# 102711.net
KiCad netlist of a schematic drawn in Altium Designer
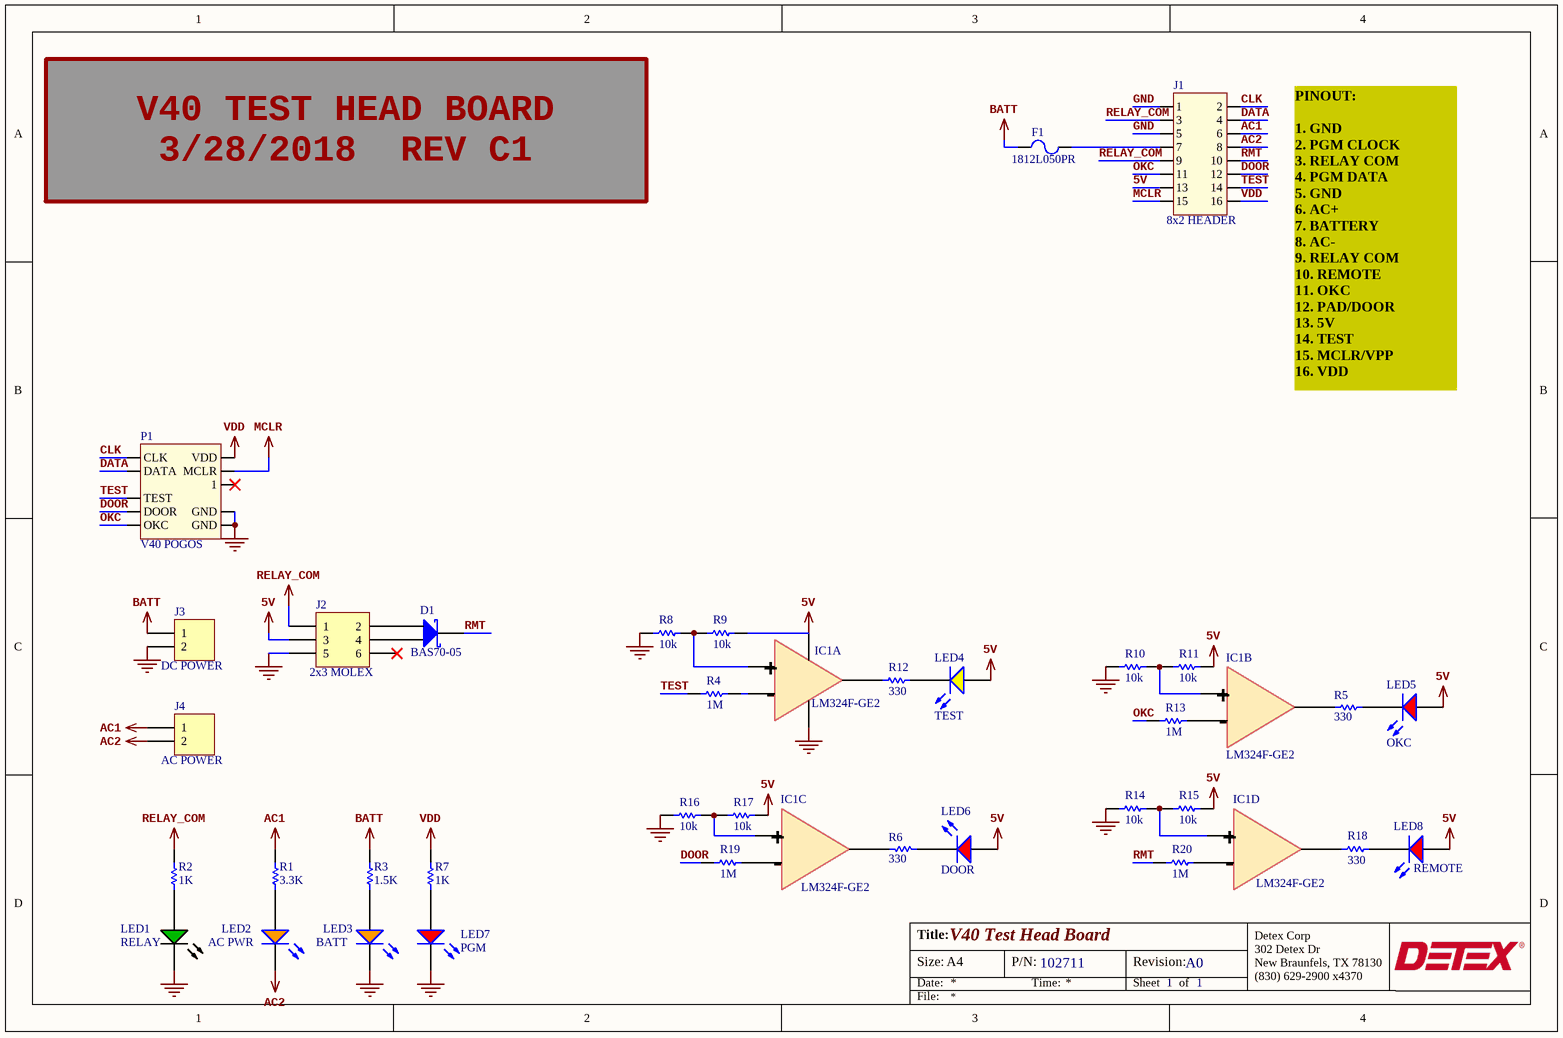
[diagram p0: 102711.SchDoc]

(export (version "E")
  (design (tool "Eeschema 10.0.6"))
  (components
    (comp (ref "D1")
      (value "BAS70-05")
      (footprint "SOT-23_M")
      (description "Dual Schottky Diode")
      (fields (field (name "MFR") "DIODES, INC"))
      (libsource (lib "Miscellaneous Devices") (part "D Schottky"))
    )
    (comp (ref "F1")
      (value "1812L050PR")
      (footprint "LFUS-1812L050_V")
      (fields (field (name "TOLERANCE") "1%"))
      (libsource (lib "Altium Content Vault") (part "CMP-1700-00002-1"))
    )
    (comp (ref "IC1")
      (value "LM324F-GE2")
      (footprint "SOIC14")
      (description "Quad Operational Amplifier 3-32V")
      (libsource (lib "102711") (part "LM324F-GE2_1"))
    )
    (comp (ref "J1")
      (value "2x8 Header")
      (footprint "HDR2X8")
      (fields (field (name "DESC") "8x2 HEADER"))
      (libsource (lib "102709") (part "2x9 Header"))
    )
    (comp (ref "J2")
      (value "2x3 MOLEX")
      (footprint "HDR2X3")
      (description "Header, 3-Pin, Dual row")
      (fields (field (name "PUBLISHER") "Altium Limited"))
      (libsource (lib "Miscellaneous Connectors") (part "Header 3X2"))
    )
    (comp (ref "J3")
      (value "DC POWER")
      (footprint "BAT_CONN")
      (description "Header, 2-Pin")
      (fields (field (name "PUBLISHER") "Altium Limited"))
      (libsource (lib "Miscellaneous Connectors") (part "Header 2"))
    )
    (comp (ref "J4")
      (value "AC POWER")
      (footprint "HDR1X2")
      (description "Header, 2-Pin")
      (fields (field (name "PUBLISHER") "Altium Limited"))
      (libsource (lib "Miscellaneous Connectors") (part "Header 2"))
    )
    (comp (ref "LED1")
      (value "RELAY")
      (footprint "LTST-C170YKT_V")
      (description "LED Uni-Color Green, 100 mW, 5 V, -55 to 85 degC, 2-Pin SMD, RoHS, Tape and Reel")
      (libsource (lib "altium-import") (part "root_3_CMP-1674-00007-1_"))
    )
    (comp (ref "LED2")
      (value "AC PWR")
      (footprint "LTST-C170YKT_V")
      (libsource (lib "altium-import") (part "root_3_SYM-0251-00006-1_"))
    )
    (comp (ref "LED3")
      (value "BATT")
      (footprint "LTST-C170YKT_V")
      (libsource (lib "altium-import") (part "root_3_SYM-0251-00006-1_"))
    )
    (comp (ref "LED4")
      (value "TEST")
      (footprint "LTST-C170YKT_V")
      (description "LED Uni-Color Yellow, 60 mW, 80 mA, -55 to 85 degC, 2-Pin SMD, RoHS, Tape and Reel")
      (fields (field (name "MANUFACTURER") "Lite-On"))
      (libsource (lib "altium-import") (part "root_2_CMP-1674-00003-5_"))
    )
    (comp (ref "LED5")
      (value "OKC")
      (footprint "LTST-C170YKT_V")
      (description "LED Uni-Color Red, 100 mW, 200 mA, -55 to 85 degC, 2-Pin SMD, RoHS, Tape and Reel")
      (fields (field (name "MANUFACTURER") "Lite-On"))
      (libsource (lib "altium-import") (part "root_2_CMP-1674-00001-5_"))
    )
    (comp (ref "LED6")
      (value "DOOR")
      (footprint "LTST-C170YKT_V")
      (description "LED Uni-Color Red, 100 mW, 200 mA, -55 to 85 degC, 2-Pin SMD, RoHS, Tape and Reel")
      (fields (field (name "MANUFACTURER") "Lite-On"))
      (libsource (lib "altium-import") (part "root_0_mirrored_CMP-1674-00001-5_"))
    )
    (comp (ref "LED7")
      (value "PGM")
      (footprint "LTST-C170YKT_V")
      (description "LED Uni-Color Red, 100 mW, 200 mA, -55 to 85 degC, 2-Pin SMD, RoHS, Tape and Reel")
      (fields (field (name "MANUFACTURER") "Lite-On"))
      (libsource (lib "altium-import") (part "root_3_CMP-1674-00001-5_"))
    )
    (comp (ref "LED8")
      (value "REMOTE")
      (footprint "LTST-C170YKT_V")
      (description "LED Uni-Color Red, 100 mW, 200 mA, -55 to 85 degC, 2-Pin SMD, RoHS, Tape and Reel")
      (fields (field (name "MANUFACTURER") "Lite-On"))
      (libsource (lib "altium-import") (part "root_2_CMP-1674-00001-5_"))
    )
    (comp (ref "P1")
      (value "V40 POGOS")
      (footprint "V40_POGOS")
      (libsource (lib "102711") (part "V40_POGOS"))
    )
    (comp (ref "R1")
      (value "3.3K")
      (footprint "RESC0805(2012)_M")
      (description "Resistor")
      (fields (field (name "Comment") "Res1") (field (name "PUBLISHER") "Altium Limited"))
      (libsource (lib "Miscellaneous Devices") (part "Res1"))
    )
    (comp (ref "R2")
      (value "1K")
      (footprint "RESC0805(2012)_M")
      (description "Resistor")
      (fields (field (name "Comment") "Res1") (field (name "PUBLISHER") "Altium Limited"))
      (libsource (lib "Miscellaneous Devices") (part "Res1"))
    )
    (comp (ref "R3")
      (value "1.5K")
      (footprint "RESC0805(2012)_M")
      (description "Resistor")
      (fields (field (name "Comment") "Res1") (field (name "PUBLISHER") "Altium Limited"))
      (libsource (lib "Miscellaneous Devices") (part "Res1"))
    )
    (comp (ref "R4")
      (value "1M")
      (footprint "RESC0805(2012)_M")
      (description "Resistor")
      (fields (field (name "Comment") "Res1") (field (name "PUBLISHER") "Altium Limited"))
      (libsource (lib "Miscellaneous Devices") (part "Res1"))
    )
    (comp (ref "R5")
      (value "330")
      (footprint "RESC0805(2012)_M")
      (description "Resistor")
      (fields (field (name "Comment") "Res1") (field (name "PUBLISHER") "Altium Limited"))
      (libsource (lib "Miscellaneous Devices") (part "Res1"))
    )
    (comp (ref "R6")
      (value "330")
      (footprint "RESC0805(2012)_M")
      (description "Resistor")
      (fields (field (name "Comment") "Res1") (field (name "PUBLISHER") "Altium Limited"))
      (libsource (lib "Miscellaneous Devices") (part "Res1"))
    )
    (comp (ref "R7")
      (value "1K")
      (footprint "RESC0805(2012)_M")
      (description "Resistor")
      (fields (field (name "Comment") "Res1") (field (name "PUBLISHER") "Altium Limited"))
      (libsource (lib "Miscellaneous Devices") (part "Res1"))
    )
    (comp (ref "R8")
      (value "10k")
      (footprint "RESC0805(2012)_M")
      (description "Resistor")
      (fields (field (name "Comment") "Res1") (field (name "PUBLISHER") "Altium Limited"))
      (libsource (lib "Miscellaneous Devices") (part "Res1"))
    )
    (comp (ref "R9")
      (value "10k")
      (footprint "RESC0805(2012)_M")
      (description "Resistor")
      (fields (field (name "Comment") "Res1") (field (name "PUBLISHER") "Altium Limited"))
      (libsource (lib "Miscellaneous Devices") (part "Res1"))
    )
    (comp (ref "R10")
      (value "10k")
      (footprint "RESC0805(2012)_M")
      (description "Resistor")
      (fields (field (name "Comment") "Res1") (field (name "PUBLISHER") "Altium Limited"))
      (libsource (lib "Miscellaneous Devices") (part "Res1"))
    )
    (comp (ref "R11")
      (value "10k")
      (footprint "RESC0805(2012)_M")
      (description "Resistor")
      (fields (field (name "Comment") "Res1") (field (name "PUBLISHER") "Altium Limited"))
      (libsource (lib "Miscellaneous Devices") (part "Res1"))
    )
    (comp (ref "R12")
      (value "330")
      (footprint "RESC0805(2012)_M")
      (description "Resistor")
      (fields (field (name "Comment") "Res1") (field (name "PUBLISHER") "Altium Limited"))
      (libsource (lib "Miscellaneous Devices") (part "Res1"))
    )
    (comp (ref "R13")
      (value "1M")
      (footprint "RESC0805(2012)_M")
      (description "Resistor")
      (fields (field (name "Comment") "Res1") (field (name "PUBLISHER") "Altium Limited"))
      (libsource (lib "Miscellaneous Devices") (part "Res1"))
    )
    (comp (ref "R14")
      (value "10k")
      (footprint "RESC0805(2012)_M")
      (description "Resistor")
      (fields (field (name "Comment") "Res1") (field (name "PUBLISHER") "Altium Limited"))
      (libsource (lib "Miscellaneous Devices") (part "Res1"))
    )
    (comp (ref "R15")
      (value "10k")
      (footprint "RESC0805(2012)_M")
      (description "Resistor")
      (fields (field (name "Comment") "Res1") (field (name "PUBLISHER") "Altium Limited"))
      (libsource (lib "Miscellaneous Devices") (part "Res1"))
    )
    (comp (ref "R16")
      (value "10k")
      (footprint "RESC0805(2012)_M")
      (description "Resistor")
      (fields (field (name "Comment") "Res1") (field (name "PUBLISHER") "Altium Limited"))
      (libsource (lib "Miscellaneous Devices") (part "Res1"))
    )
    (comp (ref "R17")
      (value "10k")
      (footprint "RESC0805(2012)_M")
      (description "Resistor")
      (fields (field (name "Comment") "Res1") (field (name "PUBLISHER") "Altium Limited"))
      (libsource (lib "Miscellaneous Devices") (part "Res1"))
    )
    (comp (ref "R18")
      (value "330")
      (footprint "RESC0805(2012)_M")
      (description "Resistor")
      (fields (field (name "Comment") "Res1") (field (name "PUBLISHER") "Altium Limited"))
      (libsource (lib "Miscellaneous Devices") (part "Res1"))
    )
    (comp (ref "R19")
      (value "1M")
      (footprint "RESC0805(2012)_M")
      (description "Resistor")
      (fields (field (name "Comment") "Res1") (field (name "PUBLISHER") "Altium Limited"))
      (libsource (lib "Miscellaneous Devices") (part "Res1"))
    )
    (comp (ref "R20")
      (value "1M")
      (footprint "RESC0805(2012)_M")
      (description "Resistor")
      (fields (field (name "Comment") "Res1") (field (name "PUBLISHER") "Altium Limited"))
      (libsource (lib "Miscellaneous Devices") (part "Res1"))
    )
  )
  (nets
    (net (code "1") (name "/CLK") (class "Default")
      (node (ref "J1") (pin "2") (pinfunction "2_2") (pintype "passive"))
      (node (ref "P1") (pin "3") (pinfunction "CLK_3") (pintype "passive"))
    )
    (net (code "2") (name "/DATA") (class "Default")
      (node (ref "J1") (pin "4") (pinfunction "4_4") (pintype "passive"))
      (node (ref "P1") (pin "4") (pinfunction "DATA_4") (pintype "passive"))
    )
    (net (code "3") (name "/DOOR") (class "Default")
      (node (ref "J1") (pin "12") (pinfunction "12_12") (pintype "passive"))
      (node (ref "P1") (pin "9") (pinfunction "DOOR_9") (pintype "passive"))
      (node (ref "R19") (pin "1") (pinfunction "1_1") (pintype "passive"))
    )
    (net (code "4") (name "/OKC") (class "Default")
      (node (ref "J1") (pin "11") (pinfunction "11_11") (pintype "passive"))
      (node (ref "P1") (pin "10") (pinfunction "OKC_10") (pintype "passive"))
      (node (ref "R13") (pin "1") (pinfunction "1_1") (pintype "passive"))
    )
    (net (code "5") (name "/RMT") (class "Default")
      (node (ref "D1") (pin "3") (pinfunction "K_3") (pintype "passive"))
      (node (ref "J1") (pin "10") (pinfunction "10_10") (pintype "passive"))
      (node (ref "R20") (pin "1") (pinfunction "1_1") (pintype "passive"))
    )
    (net (code "6") (name "/TEST") (class "Default")
      (node (ref "J1") (pin "14") (pinfunction "14_14") (pintype "passive"))
      (node (ref "P1") (pin "7") (pinfunction "TEST_7") (pintype "passive"))
      (node (ref "R4") (pin "1") (pinfunction "1_1") (pintype "passive"))
    )
    (net (code "7") (name "5V") (class "Default")
      (node (ref "J1") (pin "13") (pinfunction "13_13") (pintype "passive"))
      (node (ref "J2") (pin "3") (pinfunction "3_3") (pintype "passive"))
      (node (ref "LED4") (pin "1") (pinfunction "A_1") (pintype "passive"))
      (node (ref "LED5") (pin "1") (pinfunction "A_1") (pintype "passive"))
      (node (ref "LED6") (pin "1") (pinfunction "A_1") (pintype "passive"))
      (node (ref "LED8") (pin "1") (pinfunction "A_1") (pintype "passive"))
      (node (ref "R11") (pin "2") (pinfunction "2_2") (pintype "passive"))
      (node (ref "R15") (pin "2") (pinfunction "2_2") (pintype "passive"))
      (node (ref "R17") (pin "2") (pinfunction "2_2") (pintype "passive"))
      (node (ref "R9") (pin "2") (pinfunction "2_2") (pintype "passive"))
    )
    (net (code "8") (name "AC1") (class "Default")
      (node (ref "J1") (pin "6") (pinfunction "6_6") (pintype "passive"))
      (node (ref "J4") (pin "1") (pinfunction "1_1") (pintype "passive"))
      (node (ref "R1") (pin "1") (pinfunction "1_1") (pintype "passive"))
    )
    (net (code "9") (name "AC2") (class "Default")
      (node (ref "J1") (pin "8") (pinfunction "8_8") (pintype "passive"))
      (node (ref "J4") (pin "2") (pinfunction "2_2") (pintype "passive"))
      (node (ref "LED2") (pin "2") (pinfunction "K_2") (pintype "passive"))
    )
    (net (code "10") (name "BATT") (class "Default")
      (node (ref "F1") (pin "1") (pinfunction "1_1") (pintype "passive"))
      (node (ref "J3") (pin "1") (pinfunction "1_1") (pintype "passive"))
      (node (ref "R3") (pin "2") (pinfunction "2_2") (pintype "passive"))
    )
    (net (code "11") (name "GND") (class "Default")
      (node (ref "IC1") (pin "4") (pinfunction "VCC_4") (pintype "power_in"))
      (node (ref "J1") (pin "1") (pinfunction "1_1") (pintype "passive"))
      (node (ref "J1") (pin "5") (pinfunction "5_5") (pintype "passive"))
      (node (ref "J2") (pin "5") (pinfunction "5_5") (pintype "passive"))
      (node (ref "J3") (pin "2") (pinfunction "2_2") (pintype "passive"))
      (node (ref "LED1") (pin "2") (pinfunction "K_2") (pintype "passive"))
      (node (ref "LED3") (pin "2") (pinfunction "K_2") (pintype "passive"))
      (node (ref "LED7") (pin "2") (pinfunction "K_2") (pintype "passive"))
      (node (ref "P1") (pin "2") (pinfunction "GND_2") (pintype "passive"))
      (node (ref "P1") (pin "8") (pinfunction "GND_8") (pintype "passive"))
      (node (ref "R10") (pin "1") (pinfunction "1_1") (pintype "passive"))
      (node (ref "R14") (pin "1") (pinfunction "1_1") (pintype "passive"))
      (node (ref "R16") (pin "1") (pinfunction "1_1") (pintype "passive"))
      (node (ref "R8") (pin "1") (pinfunction "1_1") (pintype "passive"))
    )
    (net (code "12") (name "MCLR") (class "Default")
      (node (ref "J1") (pin "15") (pinfunction "15_15") (pintype "passive"))
      (node (ref "P1") (pin "5") (pinfunction "MCLR_5") (pintype "passive"))
    )
    (net (code "13") (name "Net-(D1-A-Pad1)") (class "Default")
      (node (ref "D1") (pin "1") (pinfunction "A_1") (pintype "passive"))
      (node (ref "J2") (pin "4") (pinfunction "4_4") (pintype "passive"))
    )
    (net (code "14") (name "Net-(D1-A-Pad2)") (class "Default")
      (node (ref "D1") (pin "2") (pinfunction "A_2") (pintype "passive"))
      (node (ref "J2") (pin "2") (pinfunction "2_2") (pintype "passive"))
    )
    (net (code "15") (name "Net-(F1-Pad2)") (class "Default")
      (node (ref "F1") (pin "2") (pinfunction "2_2") (pintype "passive"))
      (node (ref "J1") (pin "7") (pinfunction "7_7") (pintype "passive"))
    )
    (net (code "16") (name "Net-(IC1A-+IN1)") (class "Default")
      (node (ref "IC1") (pin "3") (pinfunction "+IN1_3") (pintype "tri_state"))
      (node (ref "R8") (pin "2") (pinfunction "2_2") (pintype "passive"))
      (node (ref "R9") (pin "1") (pinfunction "1_1") (pintype "passive"))
    )
    (net (code "17") (name "Net-(IC1A--IN1)") (class "Default")
      (node (ref "IC1") (pin "2") (pinfunction "-IN1_2") (pintype "tri_state"))
      (node (ref "R4") (pin "2") (pinfunction "2_2") (pintype "passive"))
    )
    (net (code "18") (name "Net-(IC1A-OUT1)") (class "Default")
      (node (ref "IC1") (pin "1") (pinfunction "OUT1_1") (pintype "passive"))
      (node (ref "R12") (pin "1") (pinfunction "1_1") (pintype "passive"))
    )
    (net (code "19") (name "Net-(IC1B-+IN2)") (class "Default")
      (node (ref "IC1") (pin "5") (pinfunction "+IN2_5") (pintype "tri_state"))
      (node (ref "R10") (pin "2") (pinfunction "2_2") (pintype "passive"))
      (node (ref "R11") (pin "1") (pinfunction "1_1") (pintype "passive"))
    )
    (net (code "20") (name "Net-(IC1B--IN2)") (class "Default")
      (node (ref "IC1") (pin "6") (pinfunction "-IN2_6") (pintype "tri_state"))
      (node (ref "R13") (pin "2") (pinfunction "2_2") (pintype "passive"))
    )
    (net (code "21") (name "Net-(IC1B-OUT2)") (class "Default")
      (node (ref "IC1") (pin "7") (pinfunction "OUT2_7") (pintype "passive"))
      (node (ref "R5") (pin "2") (pinfunction "2_2") (pintype "passive"))
    )
    (net (code "22") (name "Net-(IC1C-+IN3)") (class "Default")
      (node (ref "IC1") (pin "10") (pinfunction "+IN3_10") (pintype "tri_state"))
      (node (ref "R16") (pin "2") (pinfunction "2_2") (pintype "passive"))
      (node (ref "R17") (pin "1") (pinfunction "1_1") (pintype "passive"))
    )
    (net (code "23") (name "Net-(IC1C--IN3)") (class "Default")
      (node (ref "IC1") (pin "9") (pinfunction "-IN3_9") (pintype "tri_state"))
      (node (ref "R19") (pin "2") (pinfunction "2_2") (pintype "passive"))
    )
    (net (code "24") (name "Net-(IC1C-OUT3)") (class "Default")
      (node (ref "IC1") (pin "8") (pinfunction "OUT3_8") (pintype "passive"))
      (node (ref "R6") (pin "1") (pinfunction "1_1") (pintype "passive"))
    )
    (net (code "25") (name "Net-(IC1D-+IN4)") (class "Default")
      (node (ref "IC1") (pin "12") (pinfunction "+IN4_12") (pintype "tri_state"))
      (node (ref "R14") (pin "2") (pinfunction "2_2") (pintype "passive"))
      (node (ref "R15") (pin "1") (pinfunction "1_1") (pintype "passive"))
    )
    (net (code "26") (name "Net-(IC1D--IN4)") (class "Default")
      (node (ref "IC1") (pin "13") (pinfunction "-IN4_13") (pintype "tri_state"))
      (node (ref "R20") (pin "2") (pinfunction "2_2") (pintype "passive"))
    )
    (net (code "27") (name "Net-(IC1D-OUT4)") (class "Default")
      (node (ref "IC1") (pin "14") (pinfunction "OUT4_14") (pintype "passive"))
      (node (ref "R18") (pin "1") (pinfunction "1_1") (pintype "passive"))
    )
    (net (code "28") (name "Net-(LED1-A)") (class "Default")
      (node (ref "LED1") (pin "1") (pinfunction "A_1") (pintype "passive"))
      (node (ref "R2") (pin "2") (pinfunction "2_2") (pintype "passive"))
    )
    (net (code "29") (name "Net-(LED2-A)") (class "Default")
      (node (ref "LED2") (pin "1") (pinfunction "A_1") (pintype "passive"))
      (node (ref "R1") (pin "2") (pinfunction "2_2") (pintype "passive"))
    )
    (net (code "30") (name "Net-(LED3-A)") (class "Default")
      (node (ref "LED3") (pin "1") (pinfunction "A_1") (pintype "passive"))
      (node (ref "R3") (pin "1") (pinfunction "1_1") (pintype "passive"))
    )
    (net (code "31") (name "Net-(LED4-K)") (class "Default")
      (node (ref "LED4") (pin "2") (pinfunction "K_2") (pintype "passive"))
      (node (ref "R12") (pin "2") (pinfunction "2_2") (pintype "passive"))
    )
    (net (code "32") (name "Net-(LED5-K)") (class "Default")
      (node (ref "LED5") (pin "2") (pinfunction "K_2") (pintype "passive"))
      (node (ref "R5") (pin "1") (pinfunction "1_1") (pintype "passive"))
    )
    (net (code "33") (name "Net-(LED6-K)") (class "Default")
      (node (ref "LED6") (pin "2") (pinfunction "K_2") (pintype "passive"))
      (node (ref "R6") (pin "2") (pinfunction "2_2") (pintype "passive"))
    )
    (net (code "34") (name "Net-(LED7-A)") (class "Default")
      (node (ref "LED7") (pin "1") (pinfunction "A_1") (pintype "passive"))
      (node (ref "R7") (pin "2") (pinfunction "2_2") (pintype "passive"))
    )
    (net (code "35") (name "Net-(LED8-K)") (class "Default")
      (node (ref "LED8") (pin "2") (pinfunction "K_2") (pintype "passive"))
      (node (ref "R18") (pin "2") (pinfunction "2_2") (pintype "passive"))
    )
    (net (code "36") (name "RELAY_COM") (class "Default")
      (node (ref "J1") (pin "3") (pinfunction "3_3") (pintype "passive"))
      (node (ref "J1") (pin "9") (pinfunction "9_9") (pintype "passive"))
      (node (ref "J2") (pin "1") (pinfunction "1_1") (pintype "passive"))
      (node (ref "R2") (pin "1") (pinfunction "1_1") (pintype "passive"))
    )
    (net (code "37") (name "VDD") (class "Default")
      (node (ref "J1") (pin "16") (pinfunction "16_16") (pintype "passive"))
      (node (ref "P1") (pin "6") (pinfunction "VDD_6") (pintype "passive"))
      (node (ref "R7") (pin "1") (pinfunction "1_1") (pintype "passive"))
    )
    (net (code "38") (name "unconnected-(IC1A-VEE-Pad11)") (class "Default")
      (node (ref "IC1") (pin "11") (pinfunction "VEE_11") (pintype "power_in"))
    )
    (net (code "39") (name "unconnected-(J2-Pad6)") (class "Default")
      (node (ref "J2") (pin "6") (pinfunction "6_6") (pintype "passive+no_connect"))
    )
    (net (code "40") (name "unconnected-(P1-Pad1)") (class "Default")
      (node (ref "P1") (pin "1") (pinfunction "1_1") (pintype "passive+no_connect"))
    )
  )
)
